# vio-sw.net
KiCad netlist of a schematic drawn in Altium Designer
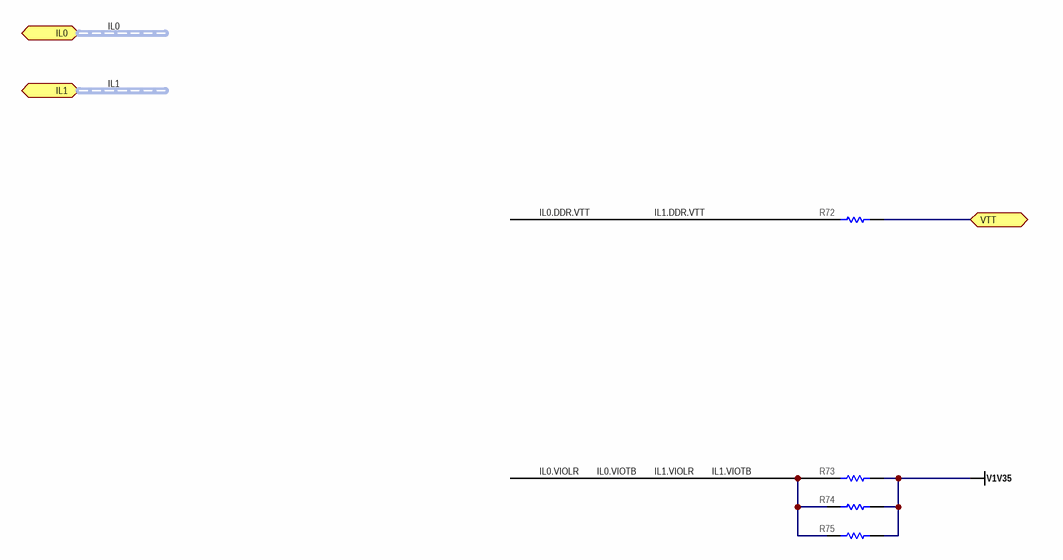
[diagram p0: vio-sw.SchDoc]

(export (version "E")
  (design (tool "Eeschema 10.0.6"))
  (components
    (comp (ref "R72")
      (value "SOLDER_LINK")
      (footprint "SOLDERLINK0603X26N")
      (description "Solder Link")
      (libsource (lib "generic") (part "RES"))
    )
    (comp (ref "R73")
      (value "SOLDER_LINK")
      (footprint "SOLDERLINK0603X26N")
      (description "Solder Link")
      (libsource (lib "generic") (part "RES"))
    )
    (comp (ref "R74")
      (value "SOLDER_LINK")
      (footprint "SOLDERLINK0603X26N")
      (description "Solder Link")
      (libsource (lib "generic") (part "RES"))
    )
    (comp (ref "R75")
      (value "SOLDER_LINK")
      (footprint "SOLDERLINK0603X26N")
      (description "Solder Link")
      (libsource (lib "generic") (part "RES"))
    )
  )
  (nets
    (net (code "3") (name "/IL0.DDR.VTT") (class "Default")
      (node (ref "R72") (pin "2") (pinfunction "2_2") (pintype "passive"))
    )
    (net (code "4") (name "/IL0.VIOLR") (class "Default")
      (node (ref "R73") (pin "2") (pinfunction "2_2") (pintype "passive"))
      (node (ref "R74") (pin "2") (pinfunction "2_2") (pintype "passive"))
      (node (ref "R75") (pin "2") (pinfunction "2_2") (pintype "passive"))
    )
    (net (code "5") (name "/VTT") (class "Default")
      (node (ref "R72") (pin "1") (pinfunction "1_1") (pintype "passive"))
    )
    (net (code "8") (name "V1V35") (class "Default")
      (node (ref "R73") (pin "1") (pinfunction "1_1") (pintype "passive"))
      (node (ref "R74") (pin "1") (pinfunction "1_1") (pintype "passive"))
      (node (ref "R75") (pin "1") (pinfunction "1_1") (pintype "passive"))
    )
  )
)
